# Task_10_1_S_2020-06-05_09-16-43.net
KiCad netlist of a schematic drawn in EasyEDA
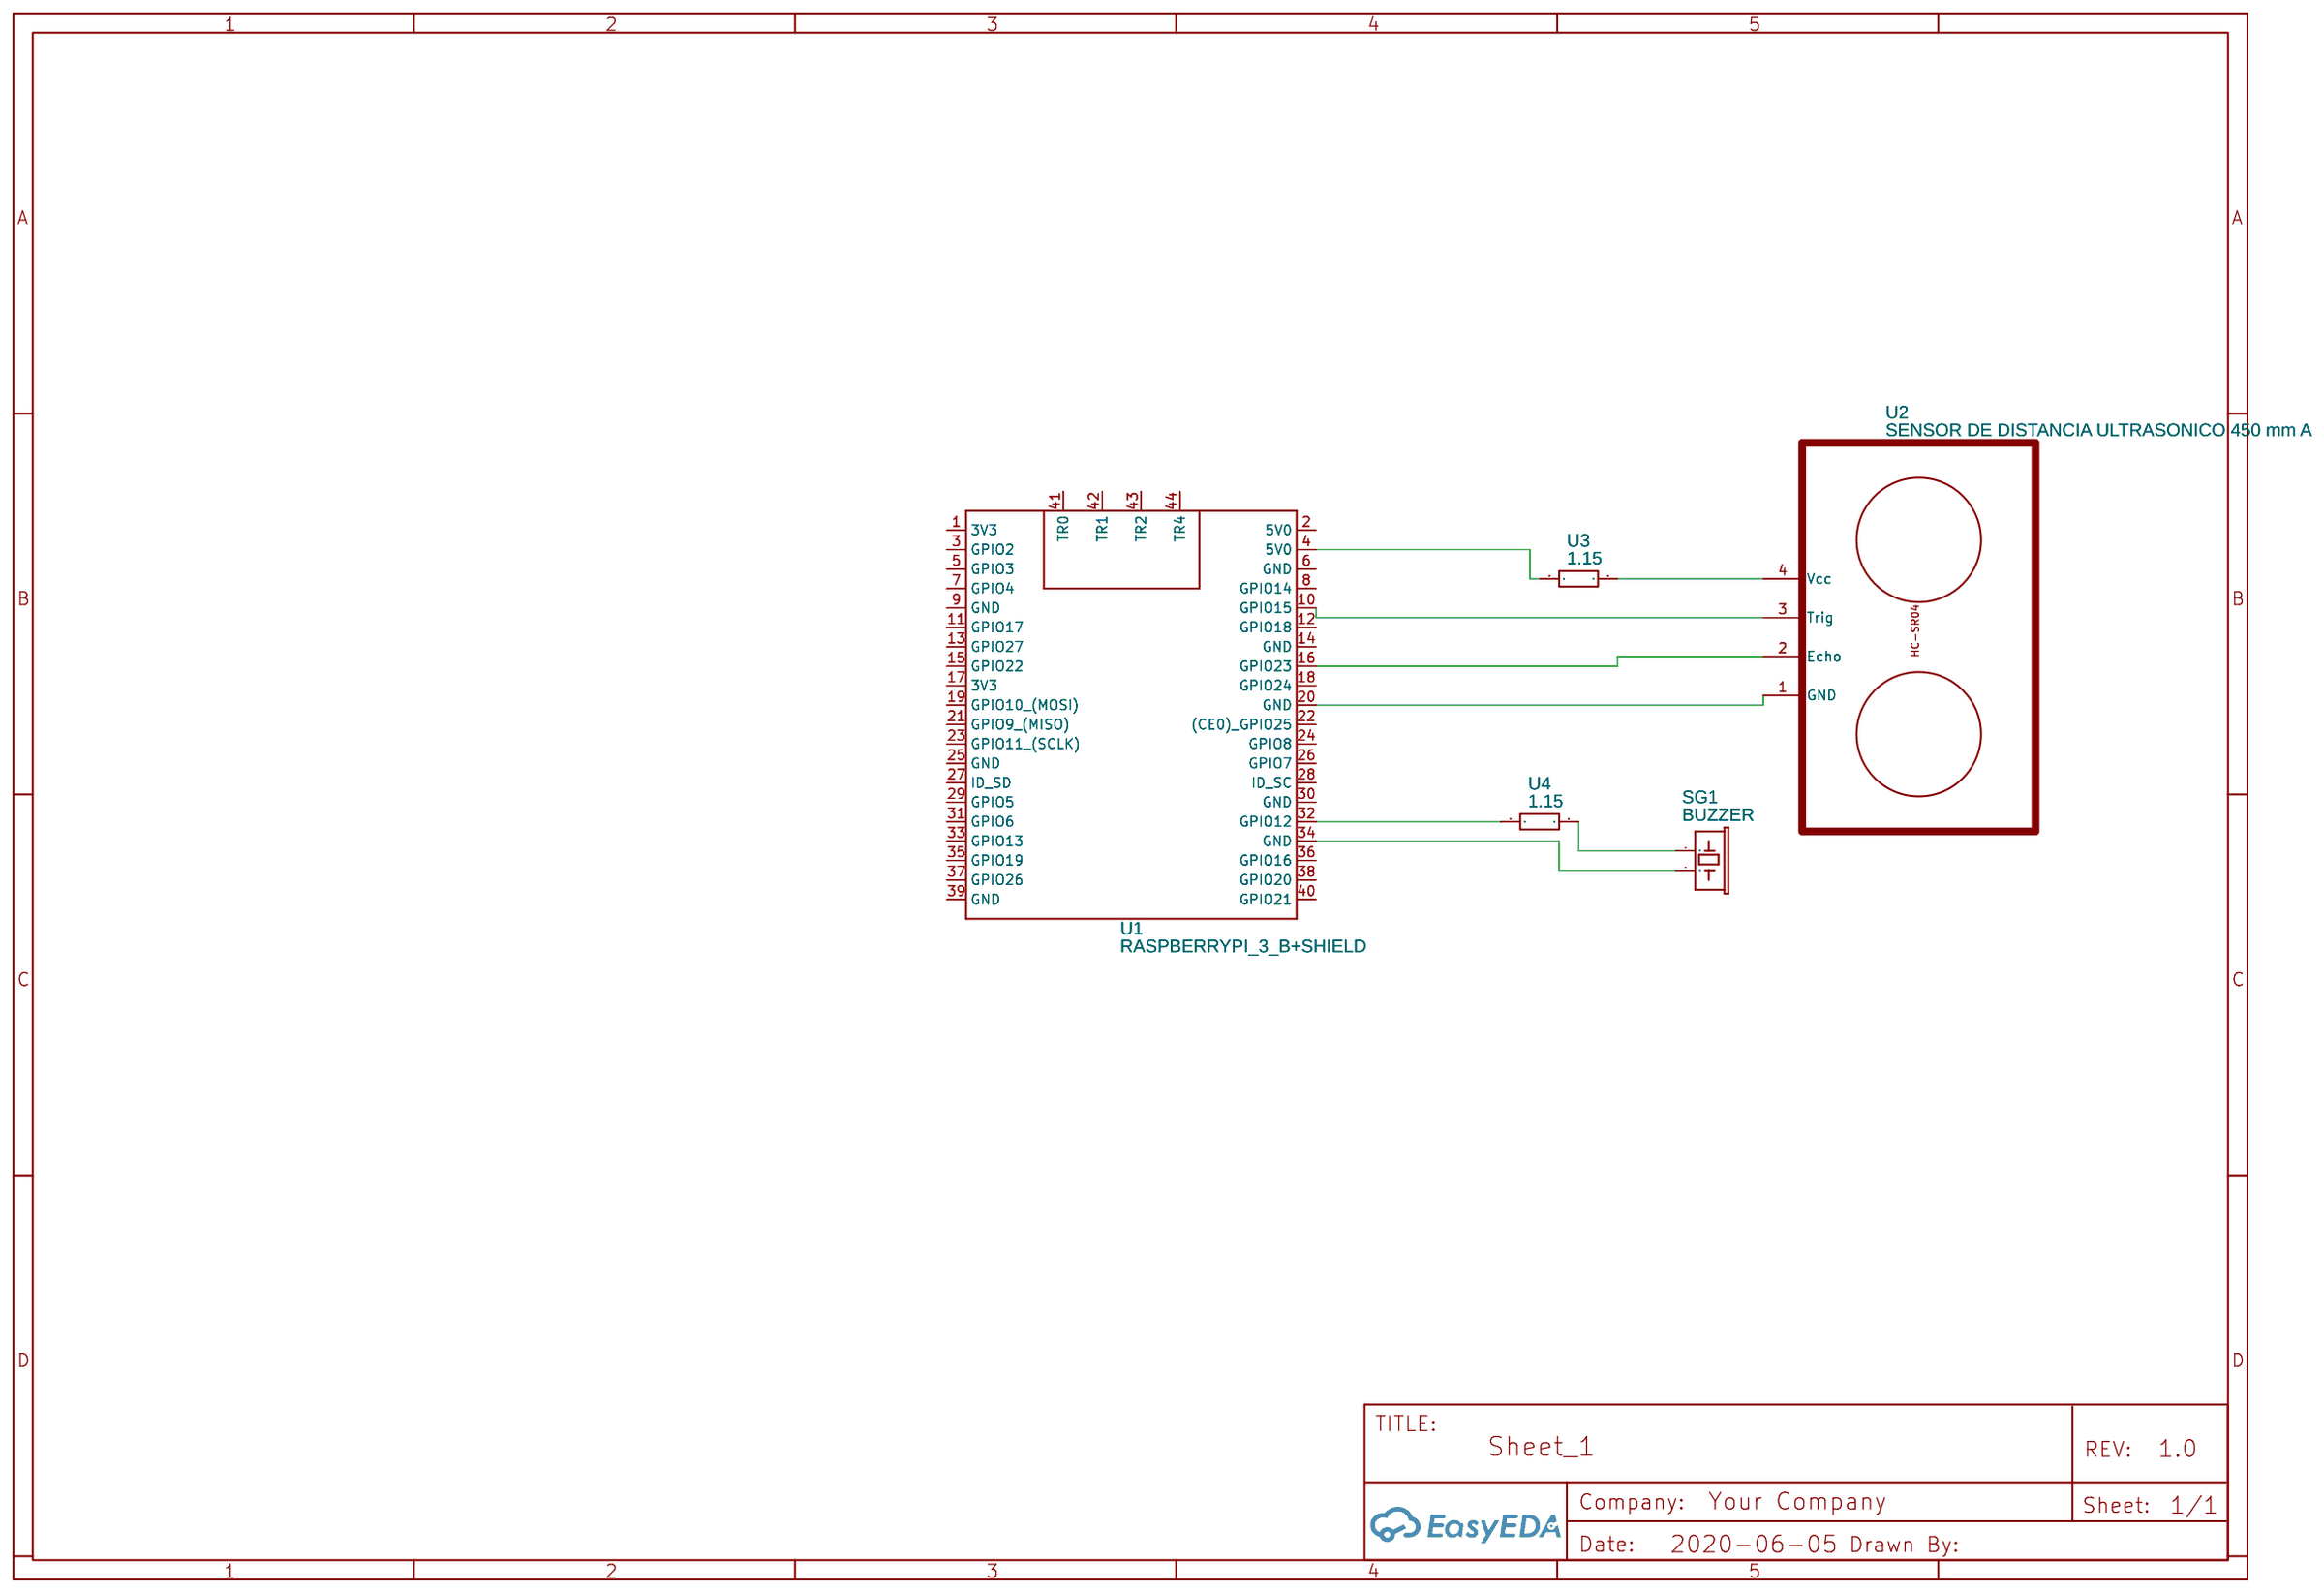
[diagram p0: schematic sheet]

(export (version "E")
  (design (tool "Eeschema 10.0.6"))
  (components
    (comp (ref "SG1") (value "BUZZER") (libsource (lib "") (part "BUZZER")))
    (comp (ref "U1")
      (value "RASPBERRYPI_3_B+SHIELD")
      (fields (field (name "BOM_Manufacturer Part") "RaspberryPi 3"))
      (libsource (lib "") (part "RASPBERRYPI_3_B+SHIELD"))
    )
    (comp (ref "U2")
      (value "SENSOR DE DISTANCIA ULTRASONICO 450 mm A")
      (libsource (lib "") (part "SENSOR DE DISTANCIA ULTRASONICO 450 mm A"))
    )
    (comp (ref "U3")
      (value "1.15")
      (fields
        (field (name "BOM_Manufacturer Part") "MELF-MFR02041/4WS1.15ΩFT50")
        (field (name "BOM_Supplier Part") "C266017")
      )
      (libsource (lib "") (part "MELF-MFR02041/4WS1.15ΩFT50"))
    )
    (comp (ref "U4")
      (value "1.15")
      (fields
        (field (name "BOM_Manufacturer Part") "MELF-MFR02041/4WS1.15ΩFT50")
        (field (name "BOM_Supplier Part") "C266017")
      )
      (libsource (lib "") (part "MELF-MFR02041/4WS1.15ΩFT50"))
    )
  )
  (nets
    (net (code "1") (name "Net-(SG1-1)") (class "Default")
      (node (ref "SG1") (pin "+") (pinfunction "1_+") (pintype "unspecified"))
      (node (ref "U4") (pin "2") (pinfunction "2_2") (pintype "unspecified"))
    )
    (net (code "2") (name "Net-(SG1-2)") (class "Default")
      (node (ref "SG1") (pin "-") (pinfunction "2_-") (pintype "unspecified"))
      (node (ref "U1") (pin "34") (pinfunction "GND_34") (pintype "unspecified"))
    )
    (net (code "3") (name "Net-(U1-5V0-Pad4)") (class "Default")
      (node (ref "U1") (pin "4") (pinfunction "5V0_4") (pintype "unspecified"))
      (node (ref "U3") (pin "1") (pinfunction "1_1") (pintype "unspecified"))
    )
    (net (code "4") (name "Net-(U1-GPIO12)") (class "Default")
      (node (ref "U1") (pin "32") (pinfunction "GPIO12_32") (pintype "unspecified"))
      (node (ref "U4") (pin "1") (pinfunction "1_1") (pintype "unspecified"))
    )
    (net (code "5") (name "Net-(U1-GPIO15)") (class "Default")
      (node (ref "U1") (pin "10") (pinfunction "GPIO15_10") (pintype "unspecified"))
      (node (ref "U2") (pin "3") (pinfunction "Trig_3") (pintype "unspecified"))
    )
    (net (code "6") (name "Net-(U1-GPIO23)") (class "Default")
      (node (ref "U1") (pin "16") (pinfunction "GPIO23_16") (pintype "unspecified"))
      (node (ref "U2") (pin "2") (pinfunction "Echo_2") (pintype "unspecified"))
    )
    (net (code "7") (name "Net-(U2-GND)") (class "Default")
      (node (ref "U1") (pin "20") (pinfunction "GND_20") (pintype "unspecified"))
      (node (ref "U2") (pin "1") (pinfunction "GND_1") (pintype "unspecified"))
    )
    (net (code "8") (name "Net-(U2-Vcc)") (class "Default")
      (node (ref "U2") (pin "4") (pinfunction "Vcc_4") (pintype "unspecified"))
      (node (ref "U3") (pin "2") (pinfunction "2_2") (pintype "unspecified"))
    )
    (net (code "9") (name "unconnected-(U1-(CE0)_GPIO25-Pad22)") (class "Default")
      (node (ref "U1") (pin "22") (pinfunction "(CE0)_GPIO25_22") (pintype "unspecified"))
    )
    (net (code "10") (name "unconnected-(U1-3V3-Pad1)") (class "Default")
      (node (ref "U1") (pin "1") (pinfunction "3V3_1") (pintype "unspecified"))
    )
    (net (code "11") (name "unconnected-(U1-3V3-Pad17)") (class "Default")
      (node (ref "U1") (pin "17") (pinfunction "3V3_17") (pintype "unspecified"))
    )
    (net (code "12") (name "unconnected-(U1-5V0-Pad2)") (class "Default")
      (node (ref "U1") (pin "2") (pinfunction "5V0_2") (pintype "unspecified"))
    )
    (net (code "13") (name "unconnected-(U1-GND-Pad6)") (class "Default")
      (node (ref "U1") (pin "6") (pinfunction "GND_6") (pintype "unspecified"))
    )
    (net (code "14") (name "unconnected-(U1-GND-Pad9)") (class "Default")
      (node (ref "U1") (pin "9") (pinfunction "GND_9") (pintype "unspecified"))
    )
    (net (code "15") (name "unconnected-(U1-GND-Pad14)") (class "Default")
      (node (ref "U1") (pin "14") (pinfunction "GND_14") (pintype "unspecified"))
    )
    (net (code "16") (name "unconnected-(U1-GND-Pad25)") (class "Default")
      (node (ref "U1") (pin "25") (pinfunction "GND_25") (pintype "unspecified"))
    )
    (net (code "17") (name "unconnected-(U1-GND-Pad30)") (class "Default")
      (node (ref "U1") (pin "30") (pinfunction "GND_30") (pintype "unspecified"))
    )
    (net (code "18") (name "unconnected-(U1-GND-Pad39)") (class "Default")
      (node (ref "U1") (pin "39") (pinfunction "GND_39") (pintype "unspecified"))
    )
    (net (code "19") (name "unconnected-(U1-GPIO2-Pad3)") (class "Default")
      (node (ref "U1") (pin "3") (pinfunction "GPIO2_3") (pintype "unspecified"))
    )
    (net (code "20") (name "unconnected-(U1-GPIO3-Pad5)") (class "Default")
      (node (ref "U1") (pin "5") (pinfunction "GPIO3_5") (pintype "unspecified"))
    )
    (net (code "21") (name "unconnected-(U1-GPIO4-Pad7)") (class "Default")
      (node (ref "U1") (pin "7") (pinfunction "GPIO4_7") (pintype "unspecified"))
    )
    (net (code "22") (name "unconnected-(U1-GPIO5-Pad29)") (class "Default")
      (node (ref "U1") (pin "29") (pinfunction "GPIO5_29") (pintype "unspecified"))
    )
    (net (code "23") (name "unconnected-(U1-GPIO6-Pad31)") (class "Default")
      (node (ref "U1") (pin "31") (pinfunction "GPIO6_31") (pintype "unspecified"))
    )
    (net (code "24") (name "unconnected-(U1-GPIO7-Pad26)") (class "Default")
      (node (ref "U1") (pin "26") (pinfunction "GPIO7_26") (pintype "unspecified"))
    )
    (net (code "25") (name "unconnected-(U1-GPIO8-Pad24)") (class "Default")
      (node (ref "U1") (pin "24") (pinfunction "GPIO8_24") (pintype "unspecified"))
    )
    (net (code "26") (name "unconnected-(U1-GPIO9_(MISO)-Pad21)") (class "Default")
      (node (ref "U1") (pin "21") (pinfunction "GPIO9_(MISO)_21") (pintype "unspecified"))
    )
    (net (code "27") (name "unconnected-(U1-GPIO10_(MOSI)-Pad19)") (class "Default")
      (node (ref "U1") (pin "19") (pinfunction "GPIO10_(MOSI)_19") (pintype "unspecified"))
    )
    (net (code "28") (name "unconnected-(U1-GPIO11_(SCLK)-Pad23)") (class "Default")
      (node (ref "U1") (pin "23") (pinfunction "GPIO11_(SCLK)_23") (pintype "unspecified"))
    )
    (net (code "29") (name "unconnected-(U1-GPIO13-Pad33)") (class "Default")
      (node (ref "U1") (pin "33") (pinfunction "GPIO13_33") (pintype "unspecified"))
    )
    (net (code "30") (name "unconnected-(U1-GPIO14-Pad8)") (class "Default")
      (node (ref "U1") (pin "8") (pinfunction "GPIO14_8") (pintype "unspecified"))
    )
    (net (code "31") (name "unconnected-(U1-GPIO16-Pad36)") (class "Default")
      (node (ref "U1") (pin "36") (pinfunction "GPIO16_36") (pintype "unspecified"))
    )
    (net (code "32") (name "unconnected-(U1-GPIO17-Pad11)") (class "Default")
      (node (ref "U1") (pin "11") (pinfunction "GPIO17_11") (pintype "unspecified"))
    )
    (net (code "33") (name "unconnected-(U1-GPIO18-Pad12)") (class "Default")
      (node (ref "U1") (pin "12") (pinfunction "GPIO18_12") (pintype "unspecified"))
    )
    (net (code "34") (name "unconnected-(U1-GPIO19-Pad35)") (class "Default")
      (node (ref "U1") (pin "35") (pinfunction "GPIO19_35") (pintype "unspecified"))
    )
    (net (code "35") (name "unconnected-(U1-GPIO20-Pad38)") (class "Default")
      (node (ref "U1") (pin "38") (pinfunction "GPIO20_38") (pintype "unspecified"))
    )
    (net (code "36") (name "unconnected-(U1-GPIO21-Pad40)") (class "Default")
      (node (ref "U1") (pin "40") (pinfunction "GPIO21_40") (pintype "unspecified"))
    )
    (net (code "37") (name "unconnected-(U1-GPIO22-Pad15)") (class "Default")
      (node (ref "U1") (pin "15") (pinfunction "GPIO22_15") (pintype "unspecified"))
    )
    (net (code "38") (name "unconnected-(U1-GPIO24-Pad18)") (class "Default")
      (node (ref "U1") (pin "18") (pinfunction "GPIO24_18") (pintype "unspecified"))
    )
    (net (code "39") (name "unconnected-(U1-GPIO26-Pad37)") (class "Default")
      (node (ref "U1") (pin "37") (pinfunction "GPIO26_37") (pintype "unspecified"))
    )
    (net (code "40") (name "unconnected-(U1-GPIO27-Pad13)") (class "Default")
      (node (ref "U1") (pin "13") (pinfunction "GPIO27_13") (pintype "unspecified"))
    )
    (net (code "41") (name "unconnected-(U1-ID_SC-Pad28)") (class "Default")
      (node (ref "U1") (pin "28") (pinfunction "ID_SC_28") (pintype "unspecified"))
    )
    (net (code "42") (name "unconnected-(U1-ID_SD-Pad27)") (class "Default")
      (node (ref "U1") (pin "27") (pinfunction "ID_SD_27") (pintype "unspecified"))
    )
    (net (code "43") (name "unconnected-(U1-TR0-Pad41)") (class "Default")
      (node (ref "U1") (pin "41") (pinfunction "TR0_41") (pintype "unspecified"))
    )
    (net (code "44") (name "unconnected-(U1-TR1-Pad42)") (class "Default")
      (node (ref "U1") (pin "42") (pinfunction "TR1_42") (pintype "unspecified"))
    )
    (net (code "45") (name "unconnected-(U1-TR2-Pad43)") (class "Default")
      (node (ref "U1") (pin "43") (pinfunction "TR2_43") (pintype "unspecified"))
    )
    (net (code "46") (name "unconnected-(U1-TR4-Pad44)") (class "Default")
      (node (ref "U1") (pin "44") (pinfunction "TR4_44") (pintype "unspecified"))
    )
  )
)
